# AnalogInterface.net
KiCad netlist of a schematic drawn in Altium Designer
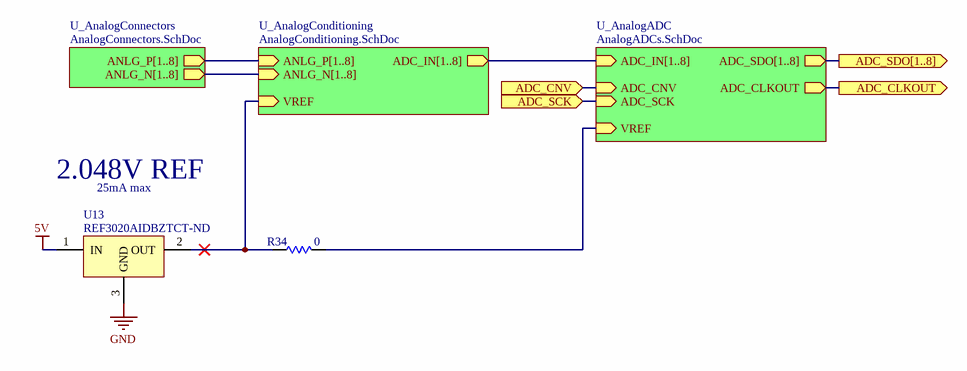
[diagram p0: AnalogInterface.SchDoc]

(export (version "E")
  (design (tool "Eeschema 10.0.6"))
  (components
    (comp (ref "R34")
      (value "0")
      (footprint "AMDC:1206-RES")
      (description "Resistor")
      (libsource (lib "AMDC") (part "Resistor"))
    )
    (comp (ref "U13")
      (value "REF3020AIDBZT")
      (footprint "AMDC:SOT23-3")
      (description "Series Voltage Reference IC ±0.2% 25mA SOT-23-3")
      (fields (field (name "SUPPLIER PART NUMBER 1") "REF3020AIDBZTCT-ND"))
      (libsource (lib "AMDC") (part "REF3020AIDBZT"))
    )
  )
  (nets
    (net (code "16") (name "/VREF") (class "Default")
      (node (ref "R34") (pin "2") (pinfunction "2_2") (pintype "passive"))
    )
    (net (code "17") (name "/VREF_1") (class "Default")
      (node (ref "R34") (pin "1") (pinfunction "1_1") (pintype "passive"))
      (node (ref "U13") (pin "2") (pinfunction "OUT_2") (pintype "passive"))
    )
    (net (code "18") (name "5V") (class "Default")
      (node (ref "U13") (pin "1") (pinfunction "IN_1") (pintype "passive"))
    )
    (net (code "19") (name "GND") (class "Default")
      (node (ref "U13") (pin "3") (pinfunction "GND_3") (pintype "passive"))
    )
  )
)
